# Amplifier_ckt_02.net
KiCad netlist of a schematic drawn in EAGLE
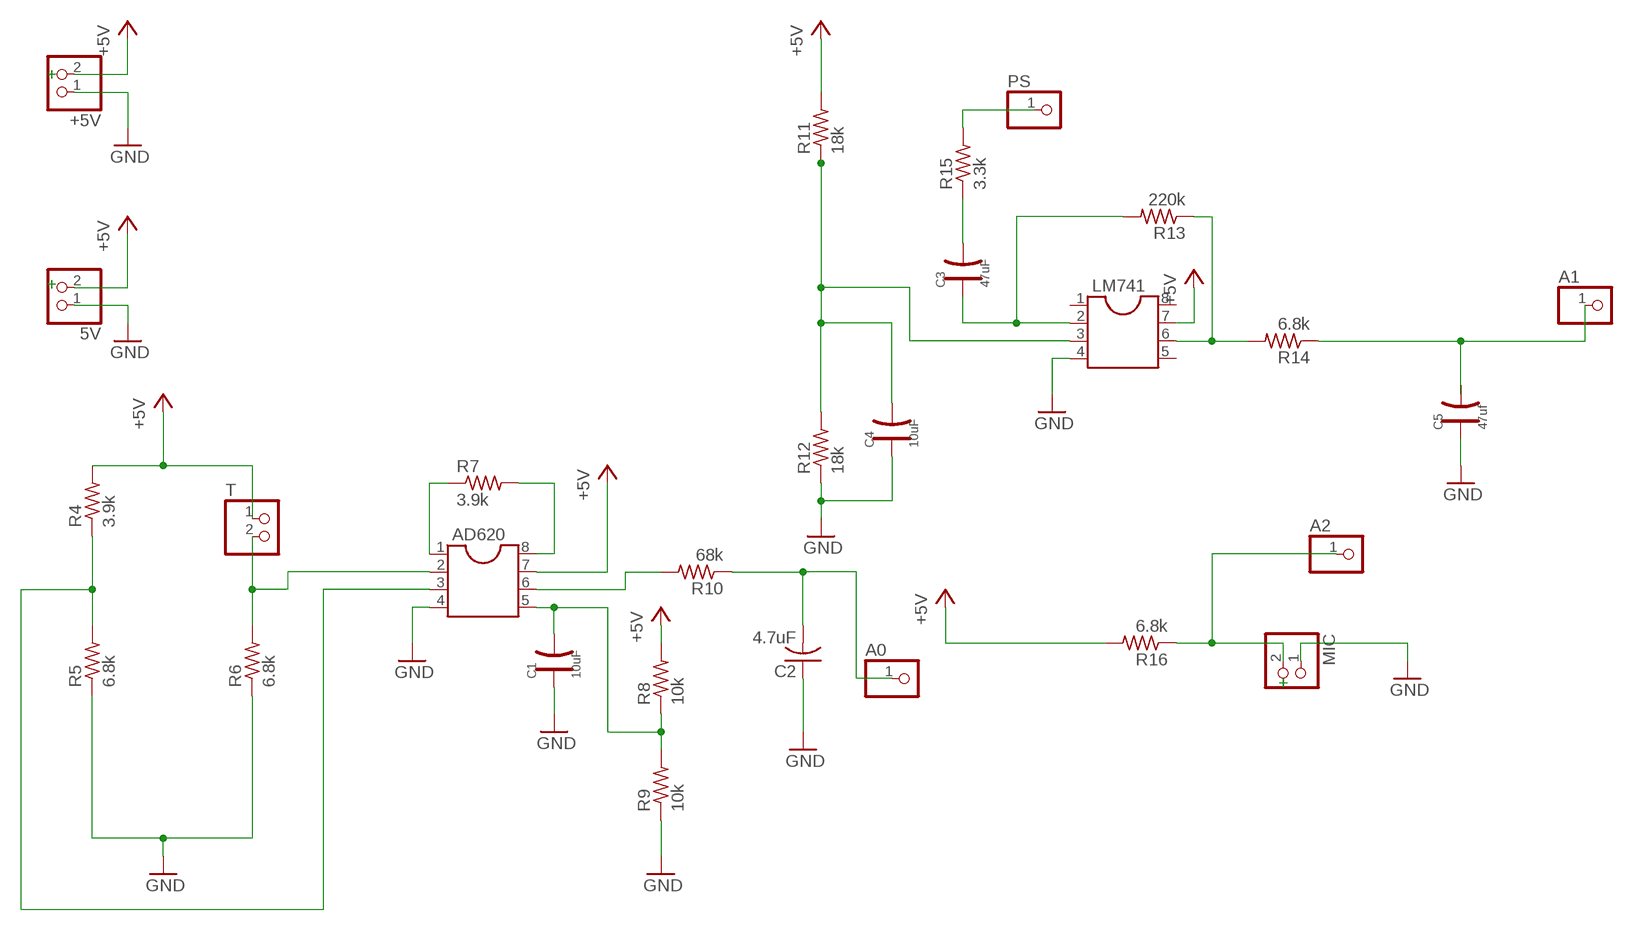
[diagram p0: schematic, sheet 1]

(export (version "E")
  (design (tool "Eeschema 10.0.6"))
  (components
    (comp (ref "+5V")
      (value "PINHD-1X2")
      (footprint "eagle-import:1X02")
      (libsource (lib "eagle-import") (part "PINHD-1X2"))
    )
    (comp (ref "5V")
      (value "PINHD-1X2")
      (footprint "eagle-import:1X02")
      (libsource (lib "eagle-import") (part "PINHD-1X2"))
    )
    (comp (ref "A0")
      (value "PINHD-1X1")
      (footprint "eagle-import:1X01")
      (libsource (lib "eagle-import") (part "PINHD-1X1"))
    )
    (comp (ref "A1")
      (value "PINHD-1X1")
      (footprint "eagle-import:1X01")
      (libsource (lib "eagle-import") (part "PINHD-1X1"))
    )
    (comp (ref "A2")
      (value "PINHD-1X1")
      (footprint "eagle-import:1X01")
      (libsource (lib "eagle-import") (part "PINHD-1X1"))
    )
    (comp (ref "AD620")
      (value "DIL8S")
      (footprint "eagle-import:SOCKET-08")
      (libsource (lib "eagle-import") (part "DIL8S"))
    )
    (comp (ref "C1")
      (value "10uF")
      (footprint "eagle-import:AVX-B")
      (libsource (lib "eagle-import") (part "CAP-POLAR-AVX-B"))
    )
    (comp (ref "C2")
      (value "4.7uF")
      (footprint "eagle-import:C0805")
      (libsource (lib "eagle-import") (part "C-USC0805"))
    )
    (comp (ref "C3")
      (value "47uF")
      (footprint "eagle-import:AVX-B")
      (libsource (lib "eagle-import") (part "CAP-POLAR-AVX-B"))
    )
    (comp (ref "C4")
      (value "10uF")
      (footprint "eagle-import:AVX-B")
      (libsource (lib "eagle-import") (part "CAP-POLAR-AVX-B"))
    )
    (comp (ref "C5")
      (value "47uf")
      (footprint "eagle-import:AVX-B")
      (libsource (lib "eagle-import") (part "CAP-POLAR-AVX-B"))
    )
    (comp (ref "LM741")
      (value "DIL8S")
      (footprint "eagle-import:SOCKET-08")
      (libsource (lib "eagle-import") (part "DIL8S"))
    )
    (comp (ref "MIC")
      (value "PINHD-1X2")
      (footprint "eagle-import:1X02")
      (libsource (lib "eagle-import") (part "PINHD-1X2"))
    )
    (comp (ref "PS")
      (value "PINHD-1X1")
      (footprint "eagle-import:1X01")
      (libsource (lib "eagle-import") (part "PINHD-1X1"))
    )
    (comp (ref "R4")
      (value "3.9k")
      (footprint "eagle-import:R0603")
      (libsource (lib "eagle-import") (part "R-US_R0603"))
    )
    (comp (ref "R5")
      (value "6.8k")
      (footprint "eagle-import:R0603")
      (libsource (lib "eagle-import") (part "R-US_R0603"))
    )
    (comp (ref "R6")
      (value "6.8k")
      (footprint "eagle-import:R0603")
      (libsource (lib "eagle-import") (part "R-US_R0603"))
    )
    (comp (ref "R7")
      (value "3.9k")
      (footprint "eagle-import:R0603")
      (libsource (lib "eagle-import") (part "R-US_R0603"))
    )
    (comp (ref "R8")
      (value "10k")
      (footprint "eagle-import:R0603")
      (libsource (lib "eagle-import") (part "R-US_R0603"))
    )
    (comp (ref "R9")
      (value "10k")
      (footprint "eagle-import:R0603")
      (libsource (lib "eagle-import") (part "R-US_R0603"))
    )
    (comp (ref "R10")
      (value "68k")
      (footprint "eagle-import:R0603")
      (libsource (lib "eagle-import") (part "R-US_R0603"))
    )
    (comp (ref "R11")
      (value "18k")
      (footprint "eagle-import:R0603")
      (libsource (lib "eagle-import") (part "R-US_R0603"))
    )
    (comp (ref "R12")
      (value "18k")
      (footprint "eagle-import:R0603")
      (libsource (lib "eagle-import") (part "R-US_R0603"))
    )
    (comp (ref "R13")
      (value "220k")
      (footprint "eagle-import:R0603")
      (libsource (lib "eagle-import") (part "R-US_R0603"))
    )
    (comp (ref "R14")
      (value "6.8k")
      (footprint "eagle-import:R0603")
      (libsource (lib "eagle-import") (part "R-US_R0603"))
    )
    (comp (ref "R15")
      (value "3.3k")
      (footprint "eagle-import:R0603")
      (libsource (lib "eagle-import") (part "R-US_R0603"))
    )
    (comp (ref "R16")
      (value "6.8k")
      (footprint "eagle-import:R0603")
      (libsource (lib "eagle-import") (part "R-US_R0603"))
    )
    (comp (ref "T")
      (value "PINHD-1X2")
      (footprint "eagle-import:1X02")
      (libsource (lib "eagle-import") (part "PINHD-1X2"))
    )
  )
  (nets
    (net (code "1") (name "+5V") (class "Default")
      (node (ref "+5V") (pin "2") (pinfunction "2_2") (pintype "passive"))
      (node (ref "5V") (pin "2") (pinfunction "2_2") (pintype "passive"))
      (node (ref "AD620") (pin "7") (pinfunction "7_7") (pintype "passive"))
      (node (ref "LM741") (pin "7") (pinfunction "7_7") (pintype "passive"))
      (node (ref "R11") (pin "2") (pinfunction "2_2") (pintype "passive"))
      (node (ref "R16") (pin "2") (pinfunction "2_2") (pintype "passive"))
      (node (ref "R4") (pin "2") (pinfunction "2_2") (pintype "passive"))
      (node (ref "R8") (pin "2") (pinfunction "2_2") (pintype "passive"))
      (node (ref "T") (pin "1") (pinfunction "1_1") (pintype "passive"))
    )
    (net (code "2") (name "GND") (class "Default")
      (node (ref "+5V") (pin "1") (pinfunction "1_1") (pintype "passive"))
      (node (ref "5V") (pin "1") (pinfunction "1_1") (pintype "passive"))
      (node (ref "AD620") (pin "4") (pinfunction "4_4") (pintype "passive"))
      (node (ref "C1") (pin "+") (pinfunction "+_+") (pintype "passive"))
      (node (ref "C2") (pin "1") (pinfunction "1_1") (pintype "passive"))
      (node (ref "C4") (pin "+") (pinfunction "+_+") (pintype "passive"))
      (node (ref "C5") (pin "+") (pinfunction "+_+") (pintype "passive"))
      (node (ref "LM741") (pin "4") (pinfunction "4_4") (pintype "passive"))
      (node (ref "MIC") (pin "1") (pinfunction "1_1") (pintype "passive"))
      (node (ref "R12") (pin "1") (pinfunction "1_1") (pintype "passive"))
      (node (ref "R5") (pin "1") (pinfunction "1_1") (pintype "passive"))
      (node (ref "R6") (pin "1") (pinfunction "1_1") (pintype "passive"))
      (node (ref "R9") (pin "1") (pinfunction "1_1") (pintype "passive"))
    )
    (net (code "3") (name "Net-(A0-Pad1)") (class "Default")
      (node (ref "A0") (pin "1") (pinfunction "1_1") (pintype "passive"))
      (node (ref "C2") (pin "2") (pinfunction "2_2") (pintype "passive"))
      (node (ref "R10") (pin "1") (pinfunction "1_1") (pintype "passive"))
    )
    (net (code "4") (name "Net-(A1-Pad1)") (class "Default")
      (node (ref "A1") (pin "1") (pinfunction "1_1") (pintype "passive"))
      (node (ref "R14") (pin "1") (pinfunction "1_1") (pintype "passive"))
    )
    (net (code "5") (name "Net-(A2-Pad1)") (class "Default")
      (node (ref "A2") (pin "1") (pinfunction "1_1") (pintype "passive"))
      (node (ref "MIC") (pin "2") (pinfunction "2_2") (pintype "passive"))
      (node (ref "R16") (pin "1") (pinfunction "1_1") (pintype "passive"))
    )
    (net (code "6") (name "Net-(AD620-Pad1)") (class "Default")
      (node (ref "AD620") (pin "1") (pinfunction "1_1") (pintype "passive"))
      (node (ref "R7") (pin "1") (pinfunction "1_1") (pintype "passive"))
    )
    (net (code "7") (name "Net-(AD620-Pad2)") (class "Default")
      (node (ref "AD620") (pin "2") (pinfunction "2_2") (pintype "passive"))
      (node (ref "R6") (pin "2") (pinfunction "2_2") (pintype "passive"))
      (node (ref "T") (pin "2") (pinfunction "2_2") (pintype "passive"))
    )
    (net (code "8") (name "Net-(AD620-Pad3)") (class "Default")
      (node (ref "AD620") (pin "3") (pinfunction "3_3") (pintype "passive"))
      (node (ref "R4") (pin "1") (pinfunction "1_1") (pintype "passive"))
      (node (ref "R5") (pin "2") (pinfunction "2_2") (pintype "passive"))
    )
    (net (code "9") (name "Net-(AD620-Pad5)") (class "Default")
      (node (ref "AD620") (pin "5") (pinfunction "5_5") (pintype "passive"))
      (node (ref "C1") (pin "-") (pinfunction "-_-") (pintype "passive"))
      (node (ref "R8") (pin "1") (pinfunction "1_1") (pintype "passive"))
      (node (ref "R9") (pin "2") (pinfunction "2_2") (pintype "passive"))
    )
    (net (code "10") (name "Net-(AD620-Pad6)") (class "Default")
      (node (ref "AD620") (pin "6") (pinfunction "6_6") (pintype "passive"))
      (node (ref "R10") (pin "2") (pinfunction "2_2") (pintype "passive"))
    )
    (net (code "11") (name "Net-(AD620-Pad8)") (class "Default")
      (node (ref "AD620") (pin "8") (pinfunction "8_8") (pintype "passive"))
      (node (ref "R7") (pin "2") (pinfunction "2_2") (pintype "passive"))
    )
    (net (code "12") (name "Net-(C3-Pad+)") (class "Default")
      (node (ref "C3") (pin "+") (pinfunction "+_+") (pintype "passive"))
      (node (ref "LM741") (pin "2") (pinfunction "2_2") (pintype "passive"))
      (node (ref "R13") (pin "2") (pinfunction "2_2") (pintype "passive"))
    )
    (net (code "13") (name "Net-(C3-Pad-)") (class "Default")
      (node (ref "C3") (pin "-") (pinfunction "-_-") (pintype "passive"))
      (node (ref "R15") (pin "1") (pinfunction "1_1") (pintype "passive"))
    )
    (net (code "14") (name "Net-(C4-Pad-)") (class "Default")
      (node (ref "C4") (pin "-") (pinfunction "-_-") (pintype "passive"))
      (node (ref "LM741") (pin "3") (pinfunction "3_3") (pintype "passive"))
      (node (ref "R11") (pin "1") (pinfunction "1_1") (pintype "passive"))
      (node (ref "R12") (pin "2") (pinfunction "2_2") (pintype "passive"))
    )
    (net (code "15") (name "Net-(LM741-Pad6)") (class "Default")
      (node (ref "LM741") (pin "6") (pinfunction "6_6") (pintype "passive"))
      (node (ref "R13") (pin "1") (pinfunction "1_1") (pintype "passive"))
      (node (ref "R14") (pin "2") (pinfunction "2_2") (pintype "passive"))
    )
    (net (code "16") (name "Net-(PS-Pad1)") (class "Default")
      (node (ref "PS") (pin "1") (pinfunction "1_1") (pintype "passive"))
      (node (ref "R15") (pin "2") (pinfunction "2_2") (pintype "passive"))
    )
    (net (code "17") (name "unconnected-(C5-Pad-)") (class "Default")
      (node (ref "C5") (pin "-") (pinfunction "-_-") (pintype "passive"))
    )
    (net (code "18") (name "unconnected-(LM741-Pad1)") (class "Default")
      (node (ref "LM741") (pin "1") (pinfunction "1_1") (pintype "passive"))
    )
    (net (code "19") (name "unconnected-(LM741-Pad5)") (class "Default")
      (node (ref "LM741") (pin "5") (pinfunction "5_5") (pintype "passive"))
    )
    (net (code "20") (name "unconnected-(LM741-Pad8)") (class "Default")
      (node (ref "LM741") (pin "8") (pinfunction "8_8") (pintype "passive"))
    )
  )
)
